# MotherBoard.net
KiCad netlist of a schematic drawn in Altium Designer
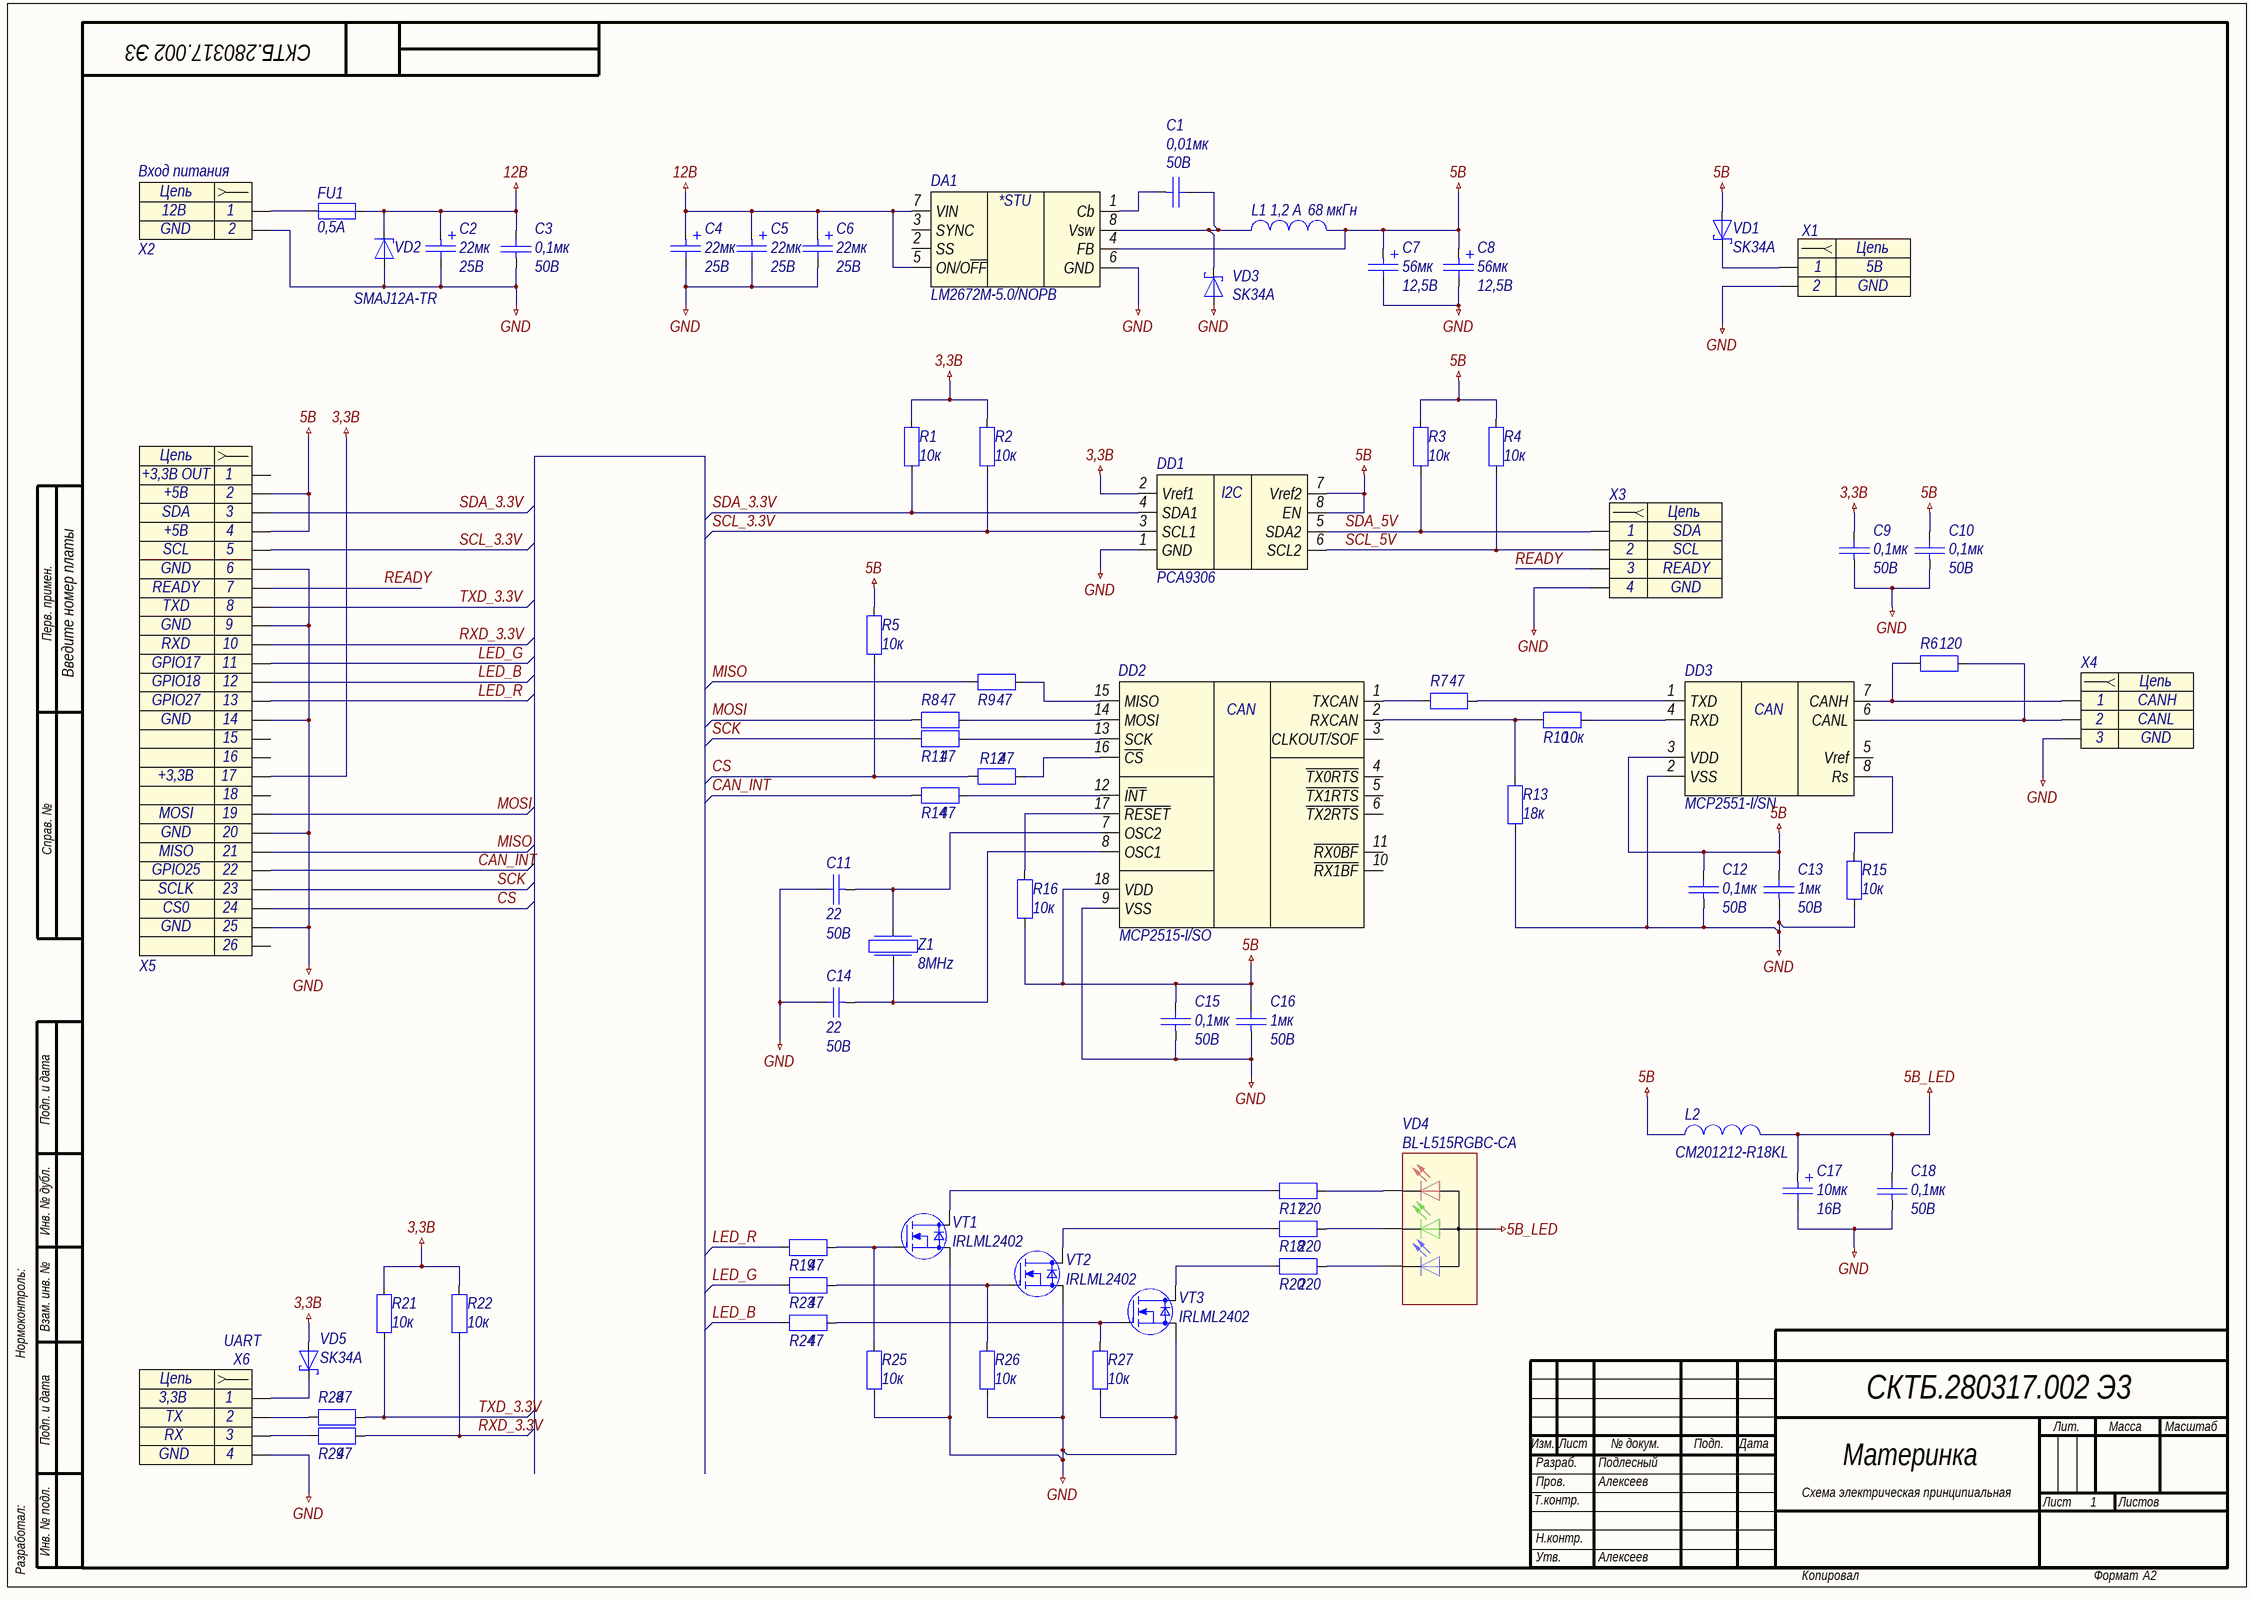
[diagram p0: MotherBoard.SchDoc]

(export (version "E")
  (design (tool "Eeschema 10.0.6"))
  (components
    (comp (ref "C1")
      (value "0,01мк")
      (footprint "ZabugorLib:C0805")
      (description "Конденсатор")
      (fields (field (name "VOLTAGE") "50В"))
      (libsource (lib "ZabugorLib") (part "Capacitor"))
    )
    (comp (ref "C2")
      (value "22мк")
      (footprint "ZabugorLib:TANTAL CASE D")
      (description "Конденсатор полярный")
      (fields (field (name "VOLTAGE") "25В"))
      (libsource (lib "ZabugorLib") (part "Capacitor_pol"))
    )
    (comp (ref "C3")
      (value "0,1мк")
      (footprint "ZabugorLib:C0805")
      (description "Конденсатор")
      (fields (field (name "VOLTAGE") "50В"))
      (libsource (lib "ZabugorLib") (part "Capacitor"))
    )
    (comp (ref "C4")
      (value "22мк")
      (footprint "ZabugorLib:TANTAL CASE D")
      (description "Конденсатор полярный")
      (fields (field (name "VOLTAGE") "25В"))
      (libsource (lib "ZabugorLib") (part "Capacitor_pol"))
    )
    (comp (ref "C5")
      (value "22мк")
      (footprint "ZabugorLib:TANTAL CASE D")
      (description "Конденсатор полярный")
      (fields (field (name "VOLTAGE") "25В"))
      (libsource (lib "ZabugorLib") (part "Capacitor_pol"))
    )
    (comp (ref "C6")
      (value "22мк")
      (footprint "ZabugorLib:TANTAL CASE D")
      (description "Конденсатор полярный")
      (fields (field (name "VOLTAGE") "25В"))
      (libsource (lib "ZabugorLib") (part "Capacitor_pol"))
    )
    (comp (ref "C7")
      (value "56мк")
      (footprint "ZabugorLib:TANTAL CASE D")
      (description "Конденсатор полярный")
      (fields (field (name "VOLTAGE") "12,5В"))
      (libsource (lib "ZabugorLib") (part "Capacitor_pol"))
    )
    (comp (ref "C8")
      (value "56мк")
      (footprint "ZabugorLib:TANTAL CASE D")
      (description "Конденсатор полярный")
      (fields (field (name "VOLTAGE") "12,5В"))
      (libsource (lib "ZabugorLib") (part "Capacitor_pol"))
    )
    (comp (ref "C9")
      (value "0,1мк")
      (footprint "ZabugorLib:C0805")
      (description "Конденсатор")
      (fields (field (name "VOLTAGE") "50В"))
      (libsource (lib "ZabugorLib") (part "Capacitor"))
    )
    (comp (ref "C10")
      (value "0,1мк")
      (footprint "ZabugorLib:C0805")
      (description "Конденсатор")
      (fields (field (name "VOLTAGE") "50В"))
      (libsource (lib "ZabugorLib") (part "Capacitor"))
    )
    (comp (ref "C11")
      (value "22")
      (footprint "ZabugorLib:C0805")
      (description "Конденсатор")
      (fields (field (name "VOLTAGE") "50В"))
      (libsource (lib "ZabugorLib") (part "Capacitor"))
    )
    (comp (ref "C12")
      (value "0,1мк")
      (footprint "ZabugorLib:C0805")
      (description "Конденсатор")
      (fields (field (name "VOLTAGE") "50В"))
      (libsource (lib "ZabugorLib") (part "Capacitor"))
    )
    (comp (ref "C13")
      (value "1мк")
      (footprint "ZabugorLib:C0805")
      (description "Конденсатор")
      (fields (field (name "VOLTAGE") "50В"))
      (libsource (lib "ZabugorLib") (part "Capacitor"))
    )
    (comp (ref "C14")
      (value "22")
      (footprint "ZabugorLib:C0805")
      (description "Конденсатор")
      (fields (field (name "VOLTAGE") "50В"))
      (libsource (lib "ZabugorLib") (part "Capacitor"))
    )
    (comp (ref "C15")
      (value "0,1мк")
      (footprint "ZabugorLib:C0805")
      (description "Конденсатор")
      (fields (field (name "VOLTAGE") "50В"))
      (libsource (lib "ZabugorLib") (part "Capacitor"))
    )
    (comp (ref "C16")
      (value "1мк")
      (footprint "ZabugorLib:C0805")
      (description "Конденсатор")
      (fields (field (name "VOLTAGE") "50В"))
      (libsource (lib "ZabugorLib") (part "Capacitor"))
    )
    (comp (ref "C17")
      (value "10мк")
      (footprint "ZabugorLib:TANTAL CASE B")
      (description "Конденсатор полярный")
      (fields (field (name "VOLTAGE") "16В"))
      (libsource (lib "ZabugorLib") (part "Capacitor_pol"))
    )
    (comp (ref "C18")
      (value "0,1мк")
      (footprint "ZabugorLib:C0805")
      (description "Конденсатор")
      (fields (field (name "VOLTAGE") "50В"))
      (libsource (lib "ZabugorLib") (part "Capacitor"))
    )
    (comp (ref "DA1")
      (value "LM2672M-5.0/NOPB")
      (footprint "ZabugorLib:SO8")
      (description "Power Converter High Efficiency 1-A Step-Down Voltage")
      (libsource (lib "ZabugorLib") (part "LM2672"))
    )
    (comp (ref "DD1")
      (value "PCA9306")
      (footprint "ZabugorLib:SSOP8")
      (description "DUAL BIDIRECTIONAL I2C BUS AND SMBus VOLTAGE-LEVEL TRANSLATOR")
      (libsource (lib "ZabugorLib") (part "PCA9306"))
    )
    (comp (ref "DD2")
      (value "MCP2515-I/SO")
      (footprint "ZabugorLib:SO-18")
      (description "CAN Controller With SPI™ Interface")
      (libsource (lib "ZabugorLib") (part "MCP2515"))
    )
    (comp (ref "DD3")
      (value "MCP2551-I/SN")
      (footprint "ZabugorLib:SO8")
      (description "High-Speed CAN Transceiver")
      (libsource (lib "ZabugorLib") (part "MCP2551"))
    )
    (comp (ref "FU1")
      (value "0,5A")
      (footprint "ZabugorLib:FUSE812")
      (description "Предохранитель")
      (fields (field (name "Comment") "MF-MSMF050"))
      (libsource (lib "ZabugorLib") (part "Fuse"))
    )
    (comp (ref "L1")
      (value "68 мкГн")
      (footprint "ZabugorLib:IND_B82464G4223M")
      (description "Катушка индуктивности")
      (fields (field (name "IMAX") "1,2 A") (field (name "Comment") "B82464G4683M"))
      (libsource (lib "ZabugorLib") (part "Inductor"))
    )
    (comp (ref "L2")
      (value "CM201212-R18KL")
      (footprint "ZabugorLib:L0805")
      (description "Катушка индуктивности")
      (fields (field (name "NAME") "CM201212-R18KL"))
      (libsource (lib "ZabugorLib") (part "Inductor"))
    )
    (comp (ref "R1")
      (value "10к")
      (footprint "ZabugorLib:R0805")
      (description "Резистор")
      (libsource (lib "ZabugorLib") (part "Resistor"))
    )
    (comp (ref "R2")
      (value "10к")
      (footprint "ZabugorLib:R0805")
      (description "Резистор")
      (libsource (lib "ZabugorLib") (part "Resistor"))
    )
    (comp (ref "R3")
      (value "10к")
      (footprint "ZabugorLib:R0805")
      (description "Резистор")
      (libsource (lib "ZabugorLib") (part "Resistor"))
    )
    (comp (ref "R4")
      (value "10к")
      (footprint "ZabugorLib:R0805")
      (description "Резистор")
      (libsource (lib "ZabugorLib") (part "Resistor"))
    )
    (comp (ref "R5")
      (value "10к")
      (footprint "ZabugorLib:R0805")
      (description "Резистор")
      (libsource (lib "ZabugorLib") (part "Resistor"))
    )
    (comp (ref "R6")
      (value "120")
      (footprint "ZabugorLib:R0805")
      (description "Резистор")
      (libsource (lib "") (part "Resistor_1"))
    )
    (comp (ref "R7")
      (value "47")
      (footprint "ZabugorLib:R0805")
      (description "Резистор")
      (libsource (lib "") (part "Resistor_1"))
    )
    (comp (ref "R8")
      (value "47")
      (footprint "ZabugorLib:R0805")
      (description "Резистор")
      (libsource (lib "") (part "Resistor_1"))
    )
    (comp (ref "R9")
      (value "47")
      (footprint "ZabugorLib:R0805")
      (description "Резистор")
      (libsource (lib "") (part "Resistor_1"))
    )
    (comp (ref "R10")
      (value "10к")
      (footprint "ZabugorLib:R0805")
      (description "Резистор")
      (libsource (lib "") (part "Resistor_1"))
    )
    (comp (ref "R11")
      (value "47")
      (footprint "ZabugorLib:R0805")
      (description "Резистор")
      (libsource (lib "") (part "Resistor_1"))
    )
    (comp (ref "R12")
      (value "47")
      (footprint "ZabugorLib:R0805")
      (description "Резистор")
      (libsource (lib "") (part "Resistor_1"))
    )
    (comp (ref "R13")
      (value "18к")
      (footprint "ZabugorLib:R0805")
      (description "Резистор")
      (libsource (lib "ZabugorLib") (part "Resistor"))
    )
    (comp (ref "R14")
      (value "47")
      (footprint "ZabugorLib:R0805")
      (description "Резистор")
      (libsource (lib "") (part "Resistor_1"))
    )
    (comp (ref "R15")
      (value "10к")
      (footprint "ZabugorLib:R0805")
      (description "Резистор")
      (libsource (lib "ZabugorLib") (part "Resistor"))
    )
    (comp (ref "R16")
      (value "10к")
      (footprint "ZabugorLib:R0805")
      (description "Резистор")
      (libsource (lib "ZabugorLib") (part "Resistor"))
    )
    (comp (ref "R17")
      (value "220")
      (footprint "ZabugorLib:R0805")
      (description "Резистор")
      (libsource (lib "") (part "Resistor_1"))
    )
    (comp (ref "R18")
      (value "220")
      (footprint "ZabugorLib:R0805")
      (description "Резистор")
      (libsource (lib "") (part "Resistor_1"))
    )
    (comp (ref "R19")
      (value "47")
      (footprint "ZabugorLib:R0805")
      (description "Резистор")
      (libsource (lib "") (part "Resistor_1"))
    )
    (comp (ref "R20")
      (value "220")
      (footprint "ZabugorLib:R0805")
      (description "Резистор")
      (libsource (lib "") (part "Resistor_1"))
    )
    (comp (ref "R21")
      (value "10к")
      (footprint "ZabugorLib:R0805")
      (description "Резистор")
      (libsource (lib "ZabugorLib") (part "Resistor"))
    )
    (comp (ref "R22")
      (value "10к")
      (footprint "ZabugorLib:R0805")
      (description "Резистор")
      (libsource (lib "ZabugorLib") (part "Resistor"))
    )
    (comp (ref "R23")
      (value "47")
      (footprint "ZabugorLib:R0805")
      (description "Резистор")
      (libsource (lib "") (part "Resistor_1"))
    )
    (comp (ref "R24")
      (value "47")
      (footprint "ZabugorLib:R0805")
      (description "Резистор")
      (libsource (lib "") (part "Resistor_1"))
    )
    (comp (ref "R25")
      (value "10к")
      (footprint "ZabugorLib:R0805")
      (description "Резистор")
      (libsource (lib "ZabugorLib") (part "Resistor"))
    )
    (comp (ref "R26")
      (value "10к")
      (footprint "ZabugorLib:R0805")
      (description "Резистор")
      (libsource (lib "ZabugorLib") (part "Resistor"))
    )
    (comp (ref "R27")
      (value "10к")
      (footprint "ZabugorLib:R0805")
      (description "Резистор")
      (libsource (lib "ZabugorLib") (part "Resistor"))
    )
    (comp (ref "R28")
      (value "47")
      (footprint "ZabugorLib:R0805")
      (description "Резистор")
      (libsource (lib "") (part "Resistor_1"))
    )
    (comp (ref "R29")
      (value "47")
      (footprint "ZabugorLib:R0805")
      (description "Резистор")
      (libsource (lib "") (part "Resistor_1"))
    )
    (comp (ref "VD1")
      (value "SK34A")
      (footprint "ZabugorLib:SMA")
      (description "Диод Шоттки")
      (fields (field (name "NAME") "SK34A"))
      (libsource (lib "ZabugorLib") (part "DiodeSchottky"))
    )
    (comp (ref "VD2")
      (value "SMAJ12A-TR")
      (footprint "ZabugorLib:SMA")
      (description "Стабилитрон")
      (fields (field (name "NAME") "SMAJ12A-TR"))
      (libsource (lib "ZabugorLib") (part "DiodeZener"))
    )
    (comp (ref "VD3")
      (value "SK34A")
      (footprint "ZabugorLib:SMA")
      (description "Диод Шоттки")
      (fields (field (name "NAME") "SK34A"))
      (libsource (lib "ZabugorLib") (part "DiodeSchottky"))
    )
    (comp (ref "VD4")
      (value "BL-L515RGBC-CA")
      (footprint "ZabugorLib:RGB_LED")
      (description "RGB Светодиод с общим анодом")
      (fields (field (name "NAME") "BL-L515RGBC-CA"))
      (libsource (lib "ZabugorLib") (part "RGB_LED_A"))
    )
    (comp (ref "VD5")
      (value "SK34A")
      (footprint "ZabugorLib:SMA")
      (description "Диод Шоттки")
      (fields (field (name "NAME") "SK34A"))
      (libsource (lib "ZabugorLib") (part "DiodeSchottky"))
    )
    (comp (ref "VT1")
      (value "IRLML2402")
      (footprint "ZabugorLib:SOT23-3")
      (description "N-MOSFET")
      (libsource (lib "ZabugorLib") (part "N-MOSFET"))
    )
    (comp (ref "VT2")
      (value "IRLML2402")
      (footprint "ZabugorLib:SOT23-3")
      (description "N-MOSFET")
      (libsource (lib "ZabugorLib") (part "N-MOSFET"))
    )
    (comp (ref "VT3")
      (value "IRLML2402")
      (footprint "ZabugorLib:SOT23-3")
      (description "N-MOSFET")
      (libsource (lib "ZabugorLib") (part "N-MOSFET"))
    )
    (comp (ref "X1")
      (value "~")
      (footprint "ZabugorLib:MW-2M_without3D")
      (description "Разъем - 2 конт. розетка")
      (libsource (lib "") (part "Header_2_sct_1"))
    )
    (comp (ref "X2")
      (value "Вход питания")
      (footprint "ZabugorLib:MW-2M")
      (description "Разъем - 2 конт. розетка")
      (libsource (lib "ZabugorLib") (part "Header_2_sct"))
    )
    (comp (ref "X3")
      (value "~")
      (footprint "ZabugorLib:MW-4M_without3D")
      (description "Разъем - 4 конт. розетка")
      (libsource (lib "ZabugorLib") (part "Header_4_sct"))
    )
    (comp (ref "X4")
      (value "~")
      (footprint "ZabugorLib:MW-3M")
      (description "Разъем - 2 конт. розетка")
      (libsource (lib "ZabugorLib") (part "Header_3_sct"))
    )
    (comp (ref "X5")
      (value "~")
      (footprint "ZabugorLib:PLS-26")
      (description "Разъем - 5 конт. розетка")
      (libsource (lib "ZabugorLib") (part "Header_26"))
    )
    (comp (ref "X6")
      (value "UART")
      (footprint "ZabugorLib:MW-4MR")
      (description "Разъем - 4 конт. розетка")
      (fields (field (name "NAME") "UART"))
      (libsource (lib "") (part "Header_4_sct_1"))
    )
    (comp (ref "Z1")
      (value "8MHz")
      (footprint "ZabugorLib:QSMD5.0x3.2x1.0")
      (description "Кварцевый резонатор")
      (libsource (lib "ZabugorLib") (part "Crystal"))
    )
  )
  (nets
    (net (code "1") (name "/CAN_INT") (class "Default")
      (node (ref "R14") (pin "1") (pinfunction "1_1") (pintype "passive"))
      (node (ref "X5") (pin "22") (pinfunction "22_22") (pintype "passive"))
    )
    (net (code "2") (name "/CS") (class "Default")
      (node (ref "R12") (pin "1") (pinfunction "1_1") (pintype "passive"))
      (node (ref "R5") (pin "1") (pinfunction "1_1") (pintype "passive"))
      (node (ref "X5") (pin "24") (pinfunction "24_24") (pintype "passive"))
    )
    (net (code "3") (name "/LED_B") (class "Default")
      (node (ref "R24") (pin "1") (pinfunction "1_1") (pintype "passive"))
      (node (ref "X5") (pin "12") (pinfunction "12_12") (pintype "passive"))
    )
    (net (code "4") (name "/LED_G") (class "Default")
      (node (ref "R23") (pin "1") (pinfunction "1_1") (pintype "passive"))
      (node (ref "X5") (pin "11") (pinfunction "11_11") (pintype "passive"))
    )
    (net (code "5") (name "/LED_R") (class "Default")
      (node (ref "R19") (pin "1") (pinfunction "1_1") (pintype "passive"))
      (node (ref "X5") (pin "13") (pinfunction "13_13") (pintype "passive"))
    )
    (net (code "6") (name "/MISO") (class "Default")
      (node (ref "R9") (pin "1") (pinfunction "1_1") (pintype "passive"))
      (node (ref "X5") (pin "21") (pinfunction "21_21") (pintype "passive"))
    )
    (net (code "7") (name "/MOSI") (class "Default")
      (node (ref "R8") (pin "1") (pinfunction "1_1") (pintype "passive"))
      (node (ref "X5") (pin "19") (pinfunction "19_19") (pintype "passive"))
    )
    (net (code "8") (name "/READY") (class "Default")
      (node (ref "X3") (pin "3") (pinfunction "3_3") (pintype "passive"))
      (node (ref "X5") (pin "7") (pinfunction "7_7") (pintype "passive"))
    )
    (net (code "9") (name "/RXD_3.3V") (class "Default")
      (node (ref "R22") (pin "1") (pinfunction "1_1") (pintype "passive"))
      (node (ref "R29") (pin "2") (pinfunction "2_2") (pintype "passive"))
      (node (ref "X5") (pin "10") (pinfunction "10_10") (pintype "passive"))
    )
    (net (code "10") (name "/SCK") (class "Default")
      (node (ref "R11") (pin "1") (pinfunction "1_1") (pintype "passive"))
      (node (ref "X5") (pin "23") (pinfunction "23_23") (pintype "passive"))
    )
    (net (code "11") (name "/SCL_3.3V") (class "Default")
      (node (ref "DD1") (pin "3") (pinfunction "SCL1_3") (pintype "power_in"))
      (node (ref "R2") (pin "1") (pinfunction "1_1") (pintype "passive"))
      (node (ref "X5") (pin "5") (pinfunction "5_5") (pintype "passive"))
    )
    (net (code "12") (name "/SCL_5V") (class "Default")
      (node (ref "DD1") (pin "6") (pinfunction "SCL2_6") (pintype "power_in"))
      (node (ref "R4") (pin "1") (pinfunction "1_1") (pintype "passive"))
      (node (ref "X3") (pin "2") (pinfunction "2_2") (pintype "passive"))
    )
    (net (code "13") (name "/SDA_3.3V") (class "Default")
      (node (ref "DD1") (pin "4") (pinfunction "SDA1_4") (pintype "power_in"))
      (node (ref "R1") (pin "1") (pinfunction "1_1") (pintype "passive"))
      (node (ref "X5") (pin "3") (pinfunction "3_3") (pintype "passive"))
    )
    (net (code "14") (name "/SDA_5V") (class "Default")
      (node (ref "DD1") (pin "5") (pinfunction "SDA2_5") (pintype "power_in"))
      (node (ref "R3") (pin "1") (pinfunction "1_1") (pintype "passive"))
      (node (ref "X3") (pin "1") (pinfunction "1_1") (pintype "passive"))
    )
    (net (code "15") (name "/TXD_3.3V") (class "Default")
      (node (ref "R21") (pin "1") (pinfunction "1_1") (pintype "passive"))
      (node (ref "R28") (pin "2") (pinfunction "2_2") (pintype "passive"))
      (node (ref "X5") (pin "8") (pinfunction "8_8") (pintype "passive"))
    )
    (net (code "16") (name "3,3B") (class "Default")
      (node (ref "C9") (pin "2") (pinfunction "2_2") (pintype "passive"))
      (node (ref "DD1") (pin "2") (pinfunction "Vref1_2") (pintype "power_in"))
      (node (ref "R1") (pin "2") (pinfunction "2_2") (pintype "passive"))
      (node (ref "R2") (pin "2") (pinfunction "2_2") (pintype "passive"))
      (node (ref "R21") (pin "2") (pinfunction "2_2") (pintype "passive"))
      (node (ref "R22") (pin "2") (pinfunction "2_2") (pintype "passive"))
      (node (ref "VD5") (pin "2") (pinfunction "A_2") (pintype "passive"))
      (node (ref "X5") (pin "17") (pinfunction "17_17") (pintype "passive"))
    )
    (net (code "17") (name "5B") (class "Default")
      (node (ref "C10") (pin "2") (pinfunction "2_2") (pintype "passive"))
      (node (ref "C12") (pin "2") (pinfunction "2_2") (pintype "passive"))
      (node (ref "C13") (pin "2") (pinfunction "2_2") (pintype "passive"))
      (node (ref "C15") (pin "2") (pinfunction "2_2") (pintype "passive"))
      (node (ref "C16") (pin "2") (pinfunction "2_2") (pintype "passive"))
      (node (ref "C7") (pin "1") (pinfunction "1_1") (pintype "passive"))
      (node (ref "C8") (pin "1") (pinfunction "1_1") (pintype "passive"))
      (node (ref "DA1") (pin "4") (pinfunction "FB_4") (pintype "power_in"))
      (node (ref "DD1") (pin "7") (pinfunction "Vref2_7") (pintype "power_in"))
      (node (ref "DD1") (pin "8") (pinfunction "EN_8") (pintype "power_in"))
      (node (ref "DD2") (pin "18") (pinfunction "VDD_18") (pintype "power_in"))
      (node (ref "DD3") (pin "3") (pinfunction "VDD_3") (pintype "power_in"))
      (node (ref "L1") (pin "2") (pinfunction "2_2") (pintype "passive"))
      (node (ref "L2") (pin "1") (pinfunction "1_1") (pintype "passive"))
      (node (ref "R16") (pin "1") (pinfunction "1_1") (pintype "passive"))
      (node (ref "R3") (pin "2") (pinfunction "2_2") (pintype "passive"))
      (node (ref "R4") (pin "2") (pinfunction "2_2") (pintype "passive"))
      (node (ref "R5") (pin "2") (pinfunction "2_2") (pintype "passive"))
      (node (ref "VD1") (pin "2") (pinfunction "A_2") (pintype "passive"))
      (node (ref "X5") (pin "2") (pinfunction "2_2") (pintype "passive"))
      (node (ref "X5") (pin "4") (pinfunction "4_4") (pintype "passive"))
    )
    (net (code "18") (name "5B_LED") (class "Default")
      (node (ref "C17") (pin "1") (pinfunction "1_1") (pintype "passive"))
      (node (ref "C18") (pin "2") (pinfunction "2_2") (pintype "passive"))
      (node (ref "L2") (pin "2") (pinfunction "2_2") (pintype "passive"))
      (node (ref "VD4") (pin "3") (pinfunction "A_3") (pintype "passive"))
    )
    (net (code "19") (name "12B") (class "Default")
      (node (ref "C2") (pin "1") (pinfunction "1_1") (pintype "passive"))
      (node (ref "C3") (pin "2") (pinfunction "2_2") (pintype "passive"))
      (node (ref "C4") (pin "1") (pinfunction "1_1") (pintype "passive"))
      (node (ref "C5") (pin "1") (pinfunction "1_1") (pintype "passive"))
      (node (ref "C6") (pin "1") (pinfunction "1_1") (pintype "passive"))
      (node (ref "DA1") (pin "5") (pinfunction "ON/O~{FF}_5") (pintype "power_in"))
      (node (ref "DA1") (pin "7") (pinfunction "VIN_7") (pintype "power_in"))
      (node (ref "FU1") (pin "2") (pinfunction "2_2") (pintype "passive"))
      (node (ref "VD2") (pin "1") (pinfunction "K_1") (pintype "passive"))
    )
    (net (code "20") (name "GND") (class "Default")
      (node (ref "C10") (pin "1") (pinfunction "1_1") (pintype "passive"))
      (node (ref "C11") (pin "2") (pinfunction "2_2") (pintype "passive"))
      (node (ref "C12") (pin "1") (pinfunction "1_1") (pintype "passive"))
      (node (ref "C13") (pin "1") (pinfunction "1_1") (pintype "passive"))
      (node (ref "C14") (pin "2") (pinfunction "2_2") (pintype "passive"))
      (node (ref "C15") (pin "1") (pinfunction "1_1") (pintype "passive"))
      (node (ref "C16") (pin "1") (pinfunction "1_1") (pintype "passive"))
      (node (ref "C17") (pin "2") (pinfunction "2_2") (pintype "passive"))
      (node (ref "C18") (pin "1") (pinfunction "1_1") (pintype "passive"))
      (node (ref "C2") (pin "2") (pinfunction "2_2") (pintype "passive"))
      (node (ref "C3") (pin "1") (pinfunction "1_1") (pintype "passive"))
      (node (ref "C4") (pin "2") (pinfunction "2_2") (pintype "passive"))
      (node (ref "C5") (pin "2") (pinfunction "2_2") (pintype "passive"))
      (node (ref "C6") (pin "2") (pinfunction "2_2") (pintype "passive"))
      (node (ref "C7") (pin "2") (pinfunction "2_2") (pintype "passive"))
      (node (ref "C8") (pin "2") (pinfunction "2_2") (pintype "passive"))
      (node (ref "C9") (pin "1") (pinfunction "1_1") (pintype "passive"))
      (node (ref "DA1") (pin "6") (pinfunction "GND_6") (pintype "power_in"))
      (node (ref "DD1") (pin "1") (pinfunction "GND_1") (pintype "power_in"))
      (node (ref "DD2") (pin "9") (pinfunction "VSS_9") (pintype "power_in"))
      (node (ref "DD3") (pin "2") (pinfunction "VSS_2") (pintype "power_in"))
      (node (ref "R13") (pin "1") (pinfunction "1_1") (pintype "passive"))
      (node (ref "R15") (pin "1") (pinfunction "1_1") (pintype "passive"))
      (node (ref "R25") (pin "1") (pinfunction "1_1") (pintype "passive"))
      (node (ref "R26") (pin "1") (pinfunction "1_1") (pintype "passive"))
      (node (ref "R27") (pin "1") (pinfunction "1_1") (pintype "passive"))
      (node (ref "VD2") (pin "2") (pinfunction "A_2") (pintype "passive"))
      (node (ref "VD3") (pin "2") (pinfunction "A_2") (pintype "passive"))
      (node (ref "VT1") (pin "2") (pinfunction "S_2") (pintype "passive"))
      (node (ref "VT2") (pin "2") (pinfunction "S_2") (pintype "passive"))
      (node (ref "VT3") (pin "2") (pinfunction "S_2") (pintype "passive"))
      (node (ref "X1") (pin "2") (pinfunction "2_2") (pintype "passive"))
      (node (ref "X2") (pin "2") (pinfunction "2_2") (pintype "passive"))
      (node (ref "X3") (pin "4") (pinfunction "4_4") (pintype "passive"))
      (node (ref "X4") (pin "3") (pinfunction "3_3") (pintype "passive"))
      (node (ref "X5") (pin "14") (pinfunction "14_14") (pintype "passive"))
      (node (ref "X5") (pin "20") (pinfunction "20_20") (pintype "passive"))
      (node (ref "X5") (pin "25") (pinfunction "25_25") (pintype "passive"))
      (node (ref "X5") (pin "6") (pinfunction "6_6") (pintype "passive"))
      (node (ref "X5") (pin "9") (pinfunction "9_9") (pintype "passive"))
      (node (ref "X6") (pin "4") (pinfunction "4_4") (pintype "passive"))
    )
    (net (code "21") (name "Net-(DA1-Cb)") (class "Default")
      (node (ref "C1") (pin "1") (pinfunction "1_1") (pintype "passive"))
      (node (ref "DA1") (pin "1") (pinfunction "Cb_1") (pintype "power_in"))
    )
    (net (code "22") (name "Net-(DA1-Vsw)") (class "Default")
      (node (ref "C1") (pin "2") (pinfunction "2_2") (pintype "passive"))
      (node (ref "DA1") (pin "8") (pinfunction "Vsw_8") (pintype "power_in"))
      (node (ref "L1") (pin "1") (pinfunction "1_1") (pintype "passive"))
      (node (ref "VD3") (pin "1") (pinfunction "K_1") (pintype "passive"))
    )
    (net (code "23") (name "Net-(DD2-I~{NT})") (class "Default")
      (node (ref "DD2") (pin "12") (pinfunction "I~{NT}_12") (pintype "power_in"))
      (node (ref "R14") (pin "2") (pinfunction "2_2") (pintype "passive"))
    )
    (net (code "24") (name "Net-(DD2-MISO)") (class "Default")
      (node (ref "DD2") (pin "15") (pinfunction "MISO_15") (pintype "power_in"))
      (node (ref "R9") (pin "2") (pinfunction "2_2") (pintype "passive"))
    )
    (net (code "25") (name "Net-(DD2-MOSI)") (class "Default")
      (node (ref "DD2") (pin "14") (pinfunction "MOSI_14") (pintype "power_in"))
      (node (ref "R8") (pin "2") (pinfunction "2_2") (pintype "passive"))
    )
    (net (code "26") (name "Net-(DD2-OSC1)") (class "Default")
      (node (ref "C14") (pin "1") (pinfunction "1_1") (pintype "passive"))
      (node (ref "DD2") (pin "8") (pinfunction "OSC1_8") (pintype "power_in"))
      (node (ref "Z1") (pin "1") (pinfunction "1_1") (pintype "passive"))
    )
    (net (code "27") (name "Net-(DD2-OSC2)") (class "Default")
      (node (ref "C11") (pin "1") (pinfunction "1_1") (pintype "passive"))
      (node (ref "DD2") (pin "7") (pinfunction "OSC2_7") (pintype "power_in"))
      (node (ref "Z1") (pin "2") (pinfunction "2_2") (pintype "passive"))
    )
    (net (code "28") (name "Net-(DD2-RXCAN)") (class "Default")
      (node (ref "DD2") (pin "2") (pinfunction "RXCAN_2") (pintype "power_in"))
      (node (ref "R10") (pin "1") (pinfunction "1_1") (pintype "passive"))
      (node (ref "R13") (pin "2") (pinfunction "2_2") (pintype "passive"))
    )
    (net (code "29") (name "Net-(DD2-SCK)") (class "Default")
      (node (ref "DD2") (pin "13") (pinfunction "SCK_13") (pintype "power_in"))
      (node (ref "R11") (pin "2") (pinfunction "2_2") (pintype "passive"))
    )
    (net (code "30") (name "Net-(DD2-TXCAN)") (class "Default")
      (node (ref "DD2") (pin "1") (pinfunction "TXCAN_1") (pintype "power_in"))
      (node (ref "R7") (pin "1") (pinfunction "1_1") (pintype "passive"))
    )
    (net (code "31") (name "Net-(DD2-~{CS})") (class "Default")
      (node (ref "DD2") (pin "16") (pinfunction "~{CS}_16") (pintype "power_in"))
      (node (ref "R12") (pin "2") (pinfunction "2_2") (pintype "passive"))
    )
    (net (code "32") (name "Net-(DD2-~{RESET})") (class "Default")
      (node (ref "DD2") (pin "17") (pinfunction "~{RESET}_17") (pintype "power_in"))
      (node (ref "R16") (pin "2") (pinfunction "2_2") (pintype "passive"))
    )
    (net (code "33") (name "Net-(DD3-CANH)") (class "Default")
      (node (ref "DD3") (pin "7") (pinfunction "CANH_7") (pintype "power_in"))
      (node (ref "R6") (pin "1") (pinfunction "1_1") (pintype "passive"))
      (node (ref "X4") (pin "1") (pinfunction "1_1") (pintype "passive"))
    )
    (net (code "34") (name "Net-(DD3-CANL)") (class "Default")
      (node (ref "DD3") (pin "6") (pinfunction "CANL_6") (pintype "power_in"))
      (node (ref "R6") (pin "2") (pinfunction "2_2") (pintype "passive"))
      (node (ref "X4") (pin "2") (pinfunction "2_2") (pintype "passive"))
    )
    (net (code "35") (name "Net-(DD3-RXD)") (class "Default")
      (node (ref "DD3") (pin "4") (pinfunction "RXD_4") (pintype "power_in"))
      (node (ref "R10") (pin "2") (pinfunction "2_2") (pintype "passive"))
    )
    (net (code "36") (name "Net-(DD3-Rs)") (class "Default")
      (node (ref "DD3") (pin "8") (pinfunction "Rs_8") (pintype "power_in"))
      (node (ref "R15") (pin "2") (pinfunction "2_2") (pintype "passive"))
    )
    (net (code "37") (name "Net-(DD3-TXD)") (class "Default")
      (node (ref "DD3") (pin "1") (pinfunction "TXD_1") (pintype "power_in"))
      (node (ref "R7") (pin "2") (pinfunction "2_2") (pintype "passive"))
    )
    (net (code "38") (name "Net-(FU1-Pad1)") (class "Default")
      (node (ref "FU1") (pin "1") (pinfunction "1_1") (pintype "passive"))
      (node (ref "X2") (pin "1") (pinfunction "1_1") (pintype "passive"))
    )
    (net (code "39") (name "Net-(R17-Pad2)") (class "Default")
      (node (ref "R17") (pin "2") (pinfunction "2_2") (pintype "passive"))
      (node (ref "VD4") (pin "4") (pinfunction "K_4") (pintype "passive"))
    )
    (net (code "40") (name "Net-(R18-Pad2)") (class "Default")
      (node (ref "R18") (pin "2") (pinfunction "2_2") (pintype "passive"))
      (node (ref "VD4") (pin "2") (pinfunction "K_2") (pintype "passive"))
    )
    (net (code "41") (name "Net-(R20-Pad2)") (class "Default")
      (node (ref "R20") (pin "2") (pinfunction "2_2") (pintype "passive"))
      (node (ref "VD4") (pin "1") (pinfunction "K_1") (pintype "passive"))
    )
    (net (code "42") (name "Net-(R28-Pad1)") (class "Default")
      (node (ref "R28") (pin "1") (pinfunction "1_1") (pintype "passive"))
      (node (ref "X6") (pin "2") (pinfunction "2_2") (pintype "passive"))
    )
    (net (code "43") (name "Net-(R29-Pad1)") (class "Default")
      (node (ref "R29") (pin "1") (pinfunction "1_1") (pintype "passive"))
      (node (ref "X6") (pin "3") (pinfunction "3_3") (pintype "passive"))
    )
    (net (code "44") (name "Net-(VD1-K)") (class "Default")
      (node (ref "VD1") (pin "1") (pinfunction "K_1") (pintype "passive"))
      (node (ref "X1") (pin "1") (pinfunction "1_1") (pintype "passive"))
    )
    (net (code "45") (name "Net-(VD5-K)") (class "Default")
      (node (ref "VD5") (pin "1") (pinfunction "K_1") (pintype "passive"))
      (node (ref "X6") (pin "1") (pinfunction "1_1") (pintype "passive"))
    )
    (net (code "46") (name "Net-(VT1-D)") (class "Default")
      (node (ref "R17") (pin "1") (pinfunction "1_1") (pintype "passive"))
      (node (ref "VT1") (pin "3") (pinfunction "D_3") (pintype "passive"))
    )
    (net (code "47") (name "Net-(VT1-G)") (class "Default")
      (node (ref "R19") (pin "2") (pinfunction "2_2") (pintype "passive"))
      (node (ref "R25") (pin "2") (pinfunction "2_2") (pintype "passive"))
      (node (ref "VT1") (pin "1") (pinfunction "G_1") (pintype "passive"))
    )
    (net (code "48") (name "Net-(VT2-D)") (class "Default")
      (node (ref "R18") (pin "1") (pinfunction "1_1") (pintype "passive"))
      (node (ref "VT2") (pin "3") (pinfunction "D_3") (pintype "passive"))
    )
    (net (code "49") (name "Net-(VT2-G)") (class "Default")
      (node (ref "R23") (pin "2") (pinfunction "2_2") (pintype "passive"))
      (node (ref "R26") (pin "2") (pinfunction "2_2") (pintype "passive"))
      (node (ref "VT2") (pin "1") (pinfunction "G_1") (pintype "passive"))
    )
    (net (code "50") (name "Net-(VT3-D)") (class "Default")
      (node (ref "R20") (pin "1") (pinfunction "1_1") (pintype "passive"))
      (node (ref "VT3") (pin "3") (pinfunction "D_3") (pintype "passive"))
    )
    (net (code "51") (name "Net-(VT3-G)") (class "Default")
      (node (ref "R24") (pin "2") (pinfunction "2_2") (pintype "passive"))
      (node (ref "R27") (pin "2") (pinfunction "2_2") (pintype "passive"))
      (node (ref "VT3") (pin "1") (pinfunction "G_1") (pintype "passive"))
    )
    (net (code "52") (name "unconnected-(DA1-SS-Pad2)") (class "Default")
      (node (ref "DA1") (pin "2") (pinfunction "SS_2") (pintype "power_in"))
    )
    (net (code "53") (name "unconnected-(DA1-SYNC-Pad3)") (class "Default")
      (node (ref "DA1") (pin "3") (pinfunction "SYNC_3") (pintype "power_in"))
    )
    (net (code "54") (name "unconnected-(DD2-CLKOUT{slash}SOF-Pad3)") (class "Default")
      (node (ref "DD2") (pin "3") (pinfunction "CLKOUT/SOF_3") (pintype "power_in"))
    )
    (net (code "55") (name "unconnected-(DD2-~{RX0BF}-Pad11)") (class "Default")
      (node (ref "DD2") (pin "11") (pinfunction "~{RX0BF}_11") (pintype "power_in"))
    )
    (net (code "56") (name "unconnected-(DD2-~{RX1BF}-Pad10)") (class "Default")
      (node (ref "DD2") (pin "10") (pinfunction "~{RX1BF}_10") (pintype "power_in"))
    )
    (net (code "57") (name "unconnected-(DD2-~{TX0RTS}-Pad4)") (class "Default")
      (node (ref "DD2") (pin "4") (pinfunction "~{TX0RTS}_4") (pintype "power_in"))
    )
    (net (code "58") (name "unconnected-(DD2-~{TX1RTS}-Pad5)") (class "Default")
      (node (ref "DD2") (pin "5") (pinfunction "~{TX1RTS}_5") (pintype "power_in"))
    )
    (net (code "59") (name "unconnected-(DD2-~{TX2RTS}-Pad6)") (class "Default")
      (node (ref "DD2") (pin "6") (pinfunction "~{TX2RTS}_6") (pintype "power_in"))
    )
    (net (code "60") (name "unconnected-(DD3-Vref-Pad5)") (class "Default")
      (node (ref "DD3") (pin "5") (pinfunction "Vref_5") (pintype "power_in"))
    )
    (net (code "61") (name "unconnected-(X5-Pad1)") (class "Default")
      (node (ref "X5") (pin "1") (pinfunction "1_1") (pintype "passive"))
    )
    (net (code "62") (name "unconnected-(X5-Pad15)") (class "Default")
      (node (ref "X5") (pin "15") (pinfunction "15_15") (pintype "passive"))
    )
    (net (code "63") (name "unconnected-(X5-Pad16)") (class "Default")
      (node (ref "X5") (pin "16") (pinfunction "16_16") (pintype "passive"))
    )
    (net (code "64") (name "unconnected-(X5-Pad18)") (class "Default")
      (node (ref "X5") (pin "18") (pinfunction "18_18") (pintype "passive"))
    )
    (net (code "65") (name "unconnected-(X5-Pad26)") (class "Default")
      (node (ref "X5") (pin "26") (pinfunction "26_26") (pintype "passive"))
    )
  )
)
